# sensorTest.net
KiCad netlist of a schematic drawn in Altium Designer
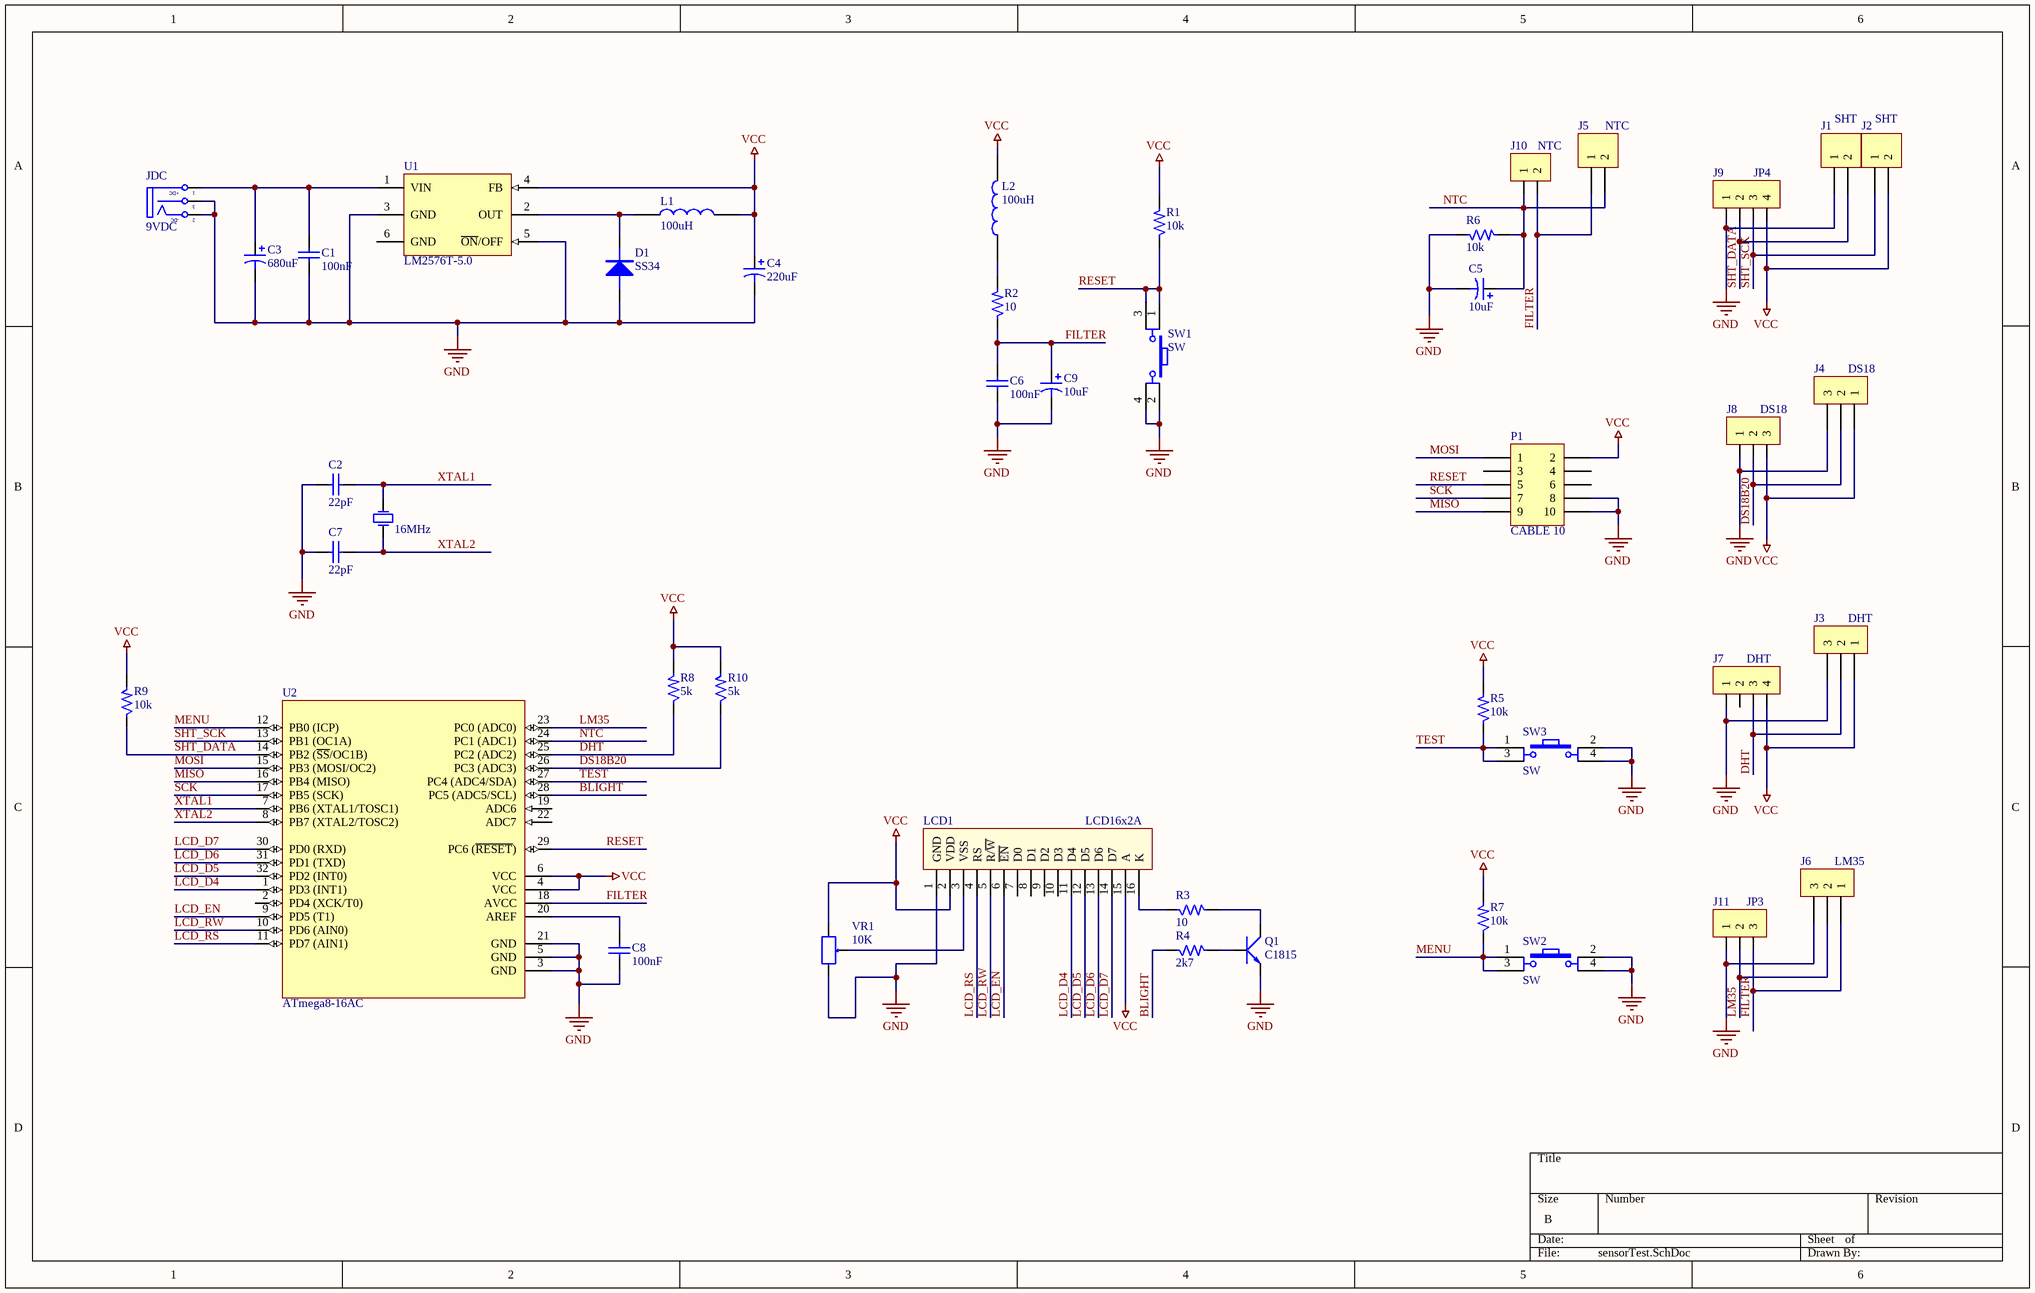
[diagram p0: sensorTest.SchDoc]

(export (version "E")
  (design (tool "Eeschema 10.0.6"))
  (components
    (comp (ref "C1")
      (value "100nF")
      (footprint "Tu 0805")
      (libsource (lib "MH_Thu Vien Du An") (part "CAP 0805"))
    )
    (comp (ref "C2")
      (value "22pF")
      (footprint "Tu 0805")
      (libsource (lib "MH_Thu Vien Du An") (part "Tu 0805"))
    )
    (comp (ref "C3")
      (value "680uF")
      (footprint "C10mm")
      (description "Polarized Capacitor (Axial)")
      (fields (field (name "PUBLISHER") "Altium Limited"))
      (libsource (lib "MH_Thu Vien Du An") (part "Cap Pol 12mm"))
    )
    (comp (ref "C4")
      (value "220uF")
      (footprint "C10mm")
      (description "Polarized Capacitor (Axial)")
      (fields (field (name "PUBLISHER") "Altium Limited"))
      (libsource (lib "MH_Thu Vien Du An") (part "Cap Pol 12mm"))
    )
    (comp (ref "C5")
      (value "10uF")
      (footprint "C5mm")
      (description "Polarized Capacitor (Axial)")
      (fields (field (name "PUBLISHER") "Altium Limited"))
      (libsource (lib "MH_Thu Vien Du An") (part "Cap Pol 5mm"))
    )
    (comp (ref "C6")
      (value "100nF")
      (footprint "Tu 0805")
      (libsource (lib "MH_Thu Vien Du An") (part "CAP 0805"))
    )
    (comp (ref "C7")
      (value "22pF")
      (footprint "Tu 0805")
      (libsource (lib "MH_Thu Vien Du An") (part "CAP 0805"))
    )
    (comp (ref "C8")
      (value "100nF")
      (footprint "Tu 0805")
      (libsource (lib "MH_Thu Vien Du An") (part "CAP 0805"))
    )
    (comp (ref "C9")
      (value "10uF")
      (footprint "C5mm")
      (description "Polarized Capacitor (Axial)")
      (fields (field (name "PUBLISHER") "Altium Limited"))
      (libsource (lib "MH_Thu Vien Du An") (part "Cap Pol 5mm"))
    )
    (comp (ref "D1")
      (value "SS34")
      (footprint "SMB")
      (description "Diode SS34 3A 40V SMA ( 1N5822 SS34A)")
      (libsource (lib "NamTEch_Lib") (part "Diode SS34 3A 40V SMA ( 1N5822 SS34A)_MH"))
    )
    (comp (ref "J1")
      (value "SHT")
      (footprint "KF2-5.08")
      (fields
        (field (name "MANUFACTURER") "Würth Elektronik eiSos GmbH")
        (field (name "PARTNO") "691103110002")
        (field (name "CREATED BY") "Karrer Zheng")
      )
      (libsource (lib "LIBRARY") (part "KF2"))
    )
    (comp (ref "J2")
      (value "SHT")
      (footprint "KF2-5.08")
      (fields
        (field (name "MANUFACTURER") "Würth Elektronik eiSos GmbH")
        (field (name "PARTNO") "691103110002")
        (field (name "CREATED BY") "Karrer Zheng")
      )
      (libsource (lib "LIBRARY") (part "KF2"))
    )
    (comp (ref "J3")
      (value "DHT")
      (footprint "KF3-5.08")
      (fields
        (field (name "MANUFACTURER") "Würth Elektronik eiSos GmbH")
        (field (name "PARTNO") "691103110003")
        (field (name "CREATED BY") "Karrer Zheng")
      )
      (libsource (lib "LIBRARY") (part "KF3"))
    )
    (comp (ref "J4")
      (value "DS18")
      (footprint "KF3-5.08")
      (fields
        (field (name "MANUFACTURER") "Würth Elektronik eiSos GmbH")
        (field (name "PARTNO") "691103110003")
        (field (name "CREATED BY") "Karrer Zheng")
      )
      (libsource (lib "LIBRARY") (part "KF3"))
    )
    (comp (ref "J5")
      (value "NTC")
      (footprint "KF2-5.08")
      (fields
        (field (name "MANUFACTURER") "Würth Elektronik eiSos GmbH")
        (field (name "PARTNO") "691103110002")
        (field (name "CREATED BY") "Karrer Zheng")
      )
      (libsource (lib "LIBRARY") (part "KF2"))
    )
    (comp (ref "J6")
      (value "LM35")
      (footprint "KF3-5.08")
      (fields
        (field (name "MANUFACTURER") "Würth Elektronik eiSos GmbH")
        (field (name "PARTNO") "691103110003")
        (field (name "CREATED BY") "Karrer Zheng")
      )
      (libsource (lib "LIBRARY") (part "KF3"))
    )
    (comp (ref "J7")
      (value "DHT")
      (footprint "JP4-C1T")
      (description "WR-PHD 2.54 mm Angled Socket Header")
      (fields
        (field (name "MANUFACTURER") "Würth Elektronik eiSos GmbH")
        (field (name "PARTNO") "613004143121")
        (field (name "CREATED BY") "Karrer Zheng")
      )
      (libsource (lib "LIBRARY") (part "JP4"))
    )
    (comp (ref "J8")
      (value "DS18")
      (footprint "JP3-C1T")
      (description "WR-PHD 2.54 mm Angled Socket Header")
      (fields
        (field (name "MANUFACTURER") "Würth Elektronik eiSos GmbH")
        (field (name "PARTNO") "613003143121")
        (field (name "CREATED BY") "Karrer Zheng")
      )
      (libsource (lib "LIBRARY") (part "JP3"))
    )
    (comp (ref "J9")
      (value "JP4")
      (footprint "JP4-C1T")
      (description "WR-PHD 2.54 mm Angled Socket Header")
      (fields
        (field (name "MANUFACTURER") "Würth Elektronik eiSos GmbH")
        (field (name "PARTNO") "613004143121")
        (field (name "CREATED BY") "Karrer Zheng")
      )
      (libsource (lib "LIBRARY") (part "JP4"))
    )
    (comp (ref "J10")
      (value "NTC")
      (footprint "JP2-C1T")
      (description "WR-PHD 2.54 mm Angled Socket Header")
      (fields
        (field (name "MANUFACTURER") "Würth Elektronik eiSos GmbH")
        (field (name "PARTNO") "613002143121")
        (field (name "CREATED BY") "Karrer Zheng")
      )
      (libsource (lib "LIBRARY") (part "JP2"))
    )
    (comp (ref "J11")
      (value "JP3")
      (footprint "JP3-C1T")
      (description "WR-PHD 2.54 mm Angled Socket Header")
      (fields
        (field (name "MANUFACTURER") "Würth Elektronik eiSos GmbH")
        (field (name "PARTNO") "613003143121")
        (field (name "CREATED BY") "Karrer Zheng")
      )
      (libsource (lib "LIBRARY") (part "JP3"))
    )
    (comp (ref "JDC")
      (value "9VDC")
      (footprint "DC-IN")
      (description "Jac DC input")
      (libsource (lib "NamTEch_Lib") (part "DCIN"))
    )
    (comp (ref "L1")
      (value "100uH")
      (footprint "Cuon Cam 7.5x7x5")
      (description "Dán")
      (libsource (lib "THU VIEN SCH_04042017_1") (part "CUON CAM 100uH_SMD"))
    )
    (comp (ref "L2")
      (value "100uH")
      (footprint "Cuon Cam 7.5x7x5")
      (description "Dán")
      (libsource (lib "") (part "CUON CAM 100uH_SMD_1"))
    )
    (comp (ref "LCD1")
      (value "LCD16x2A")
      (footprint "LCD16X2")
      (description "LCD dipslay 16 char, 2 line")
      (libsource (lib "MH_Thu Vien Du An") (part "LCD16x2"))
    )
    (comp (ref "P1")
      (value "CABLE 10")
      (footprint "CABLE 10")
      (description "Header, 5-Pin, Dual row")
      (fields (field (name "PUBLISHER") "Altium Limited"))
      (libsource (lib "MH_Thu Vien Du An") (part "CABLE 10"))
    )
    (comp (ref "Q1")
      (value "C1815")
      (footprint "SOT23B")
      (description "NPN 600mW, ECB")
      (libsource (lib "syhaunguyen") (part "C1815"))
    )
    (comp (ref "R1")
      (value "10k")
      (footprint "Tro SMD 0805")
      (description "Resistor 1/4W")
      (libsource (lib "MH_Thu Vien Du An") (part "Res"))
    )
    (comp (ref "R2")
      (value "10")
      (footprint "Tro SMD 0805")
      (description "Resistor 1/4W")
      (libsource (lib "MH_Thu Vien Du An") (part "Res"))
    )
    (comp (ref "R3")
      (value "10")
      (footprint "Tro SMD 0805")
      (description "Resistor 1/4W")
      (libsource (lib "MH_Thu Vien Du An") (part "Res"))
    )
    (comp (ref "R4")
      (value "2k7")
      (footprint "Tro SMD 0805")
      (description "Resistor 1/4W")
      (libsource (lib "MH_Thu Vien Du An") (part "Res"))
    )
    (comp (ref "R5")
      (value "10k")
      (footprint "Tro SMD 0805")
      (description "Resistor 1/4W")
      (libsource (lib "MH_Thu Vien Du An") (part "Res"))
    )
    (comp (ref "R6")
      (value "10k")
      (footprint "Tro SMD 0805")
      (description "Resistor 1/4W")
      (libsource (lib "MH_Thu Vien Du An") (part "Res"))
    )
    (comp (ref "R7")
      (value "10k")
      (footprint "Tro SMD 0805")
      (description "Resistor 1/4W")
      (libsource (lib "MH_Thu Vien Du An") (part "Res"))
    )
    (comp (ref "R8")
      (value "5k")
      (footprint "Tro SMD 0805")
      (description "Resistor 1/4W")
      (libsource (lib "MH_Thu Vien Du An") (part "Res"))
    )
    (comp (ref "R9")
      (value "10k")
      (footprint "Tro SMD 0805")
      (description "Resistor 1/4W")
      (libsource (lib "MH_Thu Vien Du An") (part "Res"))
    )
    (comp (ref "R10")
      (value "5k")
      (footprint "Tro SMD 0805")
      (description "Resistor 1/4W")
      (libsource (lib "MH_Thu Vien Du An") (part "Res"))
    )
    (comp (ref "SW1")
      (value "SW")
      (footprint "SW4")
      (description "Switch button 4 pin")
      (libsource (lib "") (part "SW4_1"))
    )
    (comp (ref "SW2")
      (value "SW")
      (footprint "SW4")
      (description "Switch button 4 pin")
      (libsource (lib "MH_Thu Vien Du An") (part "SW4"))
    )
    (comp (ref "SW3")
      (value "SW")
      (footprint "SW4")
      (description "Switch button 4 pin")
      (libsource (lib "MH_Thu Vien Du An") (part "SW4"))
    )
    (comp (ref "U1")
      (value "LM2576T-5.0")
      (footprint "LM2576SSMD")
      (description "SIMPLE SWITCHER; 3A Step-Down Voltage Regulator")
      (fields
        (field (name "MANUFACTURER") "National Semiconductor")
        (field (name "DIGIKEYPARTNUMBER") "LM2576T-5.0-ND")
        (field (name "PUBLISHER") "Altium Limited")
      )
      (libsource (lib "MH_Thu Vien Du An") (part "LM2576T-5.0"))
    )
    (comp (ref "U2")
      (value "ATmega8-16AC")
      (footprint "32A_L")
      (description "8-Bit AVR Microcontroller with 8K Bytes of In-System Programmable Flash Memory")
      (fields (field (name "PUBLISHER") "Altium Limited"))
      (libsource (lib "MH_Thu Vien Du An") (part "ATmega8-16AC"))
    )
    (comp (ref "VR1")
      (value "10K")
      (footprint "VR")
      (description "Var Resistor")
      (libsource (lib "syhaunguyen") (part "VR"))
    )
    (comp (ref "Y1")
      (value "16MHz")
      (footprint "XT2")
      (description "Crystal Oscillator")
      (fields (field (name "PUBLISHER") "Altium Limited"))
      (libsource (lib "MH_Thu Vien Du An") (part "Crystal"))
    )
  )
  (nets
    (net (code "1") (name "/BLIGHT") (class "Default")
      (node (ref "R4") (pin "1") (pinfunction "1_1") (pintype "passive"))
      (node (ref "U2") (pin "28") (pinfunction "PC5_(ADC5/SCL)_28") (pintype "bidirectional"))
    )
    (net (code "2") (name "/DHT") (class "Default")
      (node (ref "J3") (pin "2") (pinfunction "2_2") (pintype "passive"))
      (node (ref "J7") (pin "3") (pinfunction "3_3") (pintype "passive"))
      (node (ref "R8") (pin "1") (pinfunction "1_1") (pintype "passive"))
      (node (ref "U2") (pin "25") (pinfunction "PC2_(ADC2)_25") (pintype "bidirectional"))
    )
    (net (code "3") (name "/DS18B20") (class "Default")
      (node (ref "J4") (pin "2") (pinfunction "2_2") (pintype "passive"))
      (node (ref "J8") (pin "2") (pinfunction "2_2") (pintype "passive"))
      (node (ref "R10") (pin "1") (pinfunction "1_1") (pintype "passive"))
      (node (ref "U2") (pin "26") (pinfunction "PC3_(ADC3)_26") (pintype "bidirectional"))
    )
    (net (code "4") (name "/FILTER") (class "Default")
      (node (ref "C6") (pin "2") (pinfunction "2_2") (pintype "passive"))
      (node (ref "C9") (pin "1") (pinfunction "1_1") (pintype "passive"))
      (node (ref "J10") (pin "2") (pinfunction "2_2") (pintype "passive"))
      (node (ref "J11") (pin "3") (pinfunction "3_3") (pintype "passive"))
      (node (ref "J5") (pin "1") (pinfunction "1_1") (pintype "passive"))
      (node (ref "J6") (pin "1") (pinfunction "1_1") (pintype "passive"))
      (node (ref "R2") (pin "1") (pinfunction "1_1") (pintype "passive"))
      (node (ref "U2") (pin "18") (pinfunction "AVCC_18") (pintype "power_in"))
    )
    (net (code "5") (name "/LCD_D4") (class "Default")
      (node (ref "LCD1") (pin "11") (pinfunction "D4_11") (pintype "passive"))
      (node (ref "U2") (pin "1") (pinfunction "PD3_(INT1)_1") (pintype "bidirectional"))
    )
    (net (code "6") (name "/LCD_D5") (class "Default")
      (node (ref "LCD1") (pin "12") (pinfunction "D5_12") (pintype "passive"))
      (node (ref "U2") (pin "32") (pinfunction "PD2_(INT0)_32") (pintype "bidirectional"))
    )
    (net (code "7") (name "/LCD_D6") (class "Default")
      (node (ref "LCD1") (pin "13") (pinfunction "D6_13") (pintype "passive"))
      (node (ref "U2") (pin "31") (pinfunction "PD1_(TXD)_31") (pintype "bidirectional"))
    )
    (net (code "8") (name "/LCD_D7") (class "Default")
      (node (ref "LCD1") (pin "14") (pinfunction "D7_14") (pintype "passive"))
      (node (ref "U2") (pin "30") (pinfunction "PD0_(RXD)_30") (pintype "bidirectional"))
    )
    (net (code "9") (name "/LCD_EN") (class "Default")
      (node (ref "LCD1") (pin "6") (pinfunction "~{EN}_6") (pintype "passive"))
      (node (ref "U2") (pin "9") (pinfunction "PD5_(T1)_9") (pintype "bidirectional"))
    )
    (net (code "10") (name "/LCD_RS") (class "Default")
      (node (ref "LCD1") (pin "4") (pinfunction "RS_4") (pintype "passive"))
      (node (ref "U2") (pin "11") (pinfunction "PD7_(AIN1)_11") (pintype "bidirectional"))
    )
    (net (code "11") (name "/LCD_RW") (class "Default")
      (node (ref "LCD1") (pin "5") (pinfunction "R/~{W}_5") (pintype "passive"))
      (node (ref "U2") (pin "10") (pinfunction "PD6_(AIN0)_10") (pintype "bidirectional"))
    )
    (net (code "12") (name "/LM35") (class "Default")
      (node (ref "J11") (pin "2") (pinfunction "2_2") (pintype "passive"))
      (node (ref "J6") (pin "2") (pinfunction "2_2") (pintype "passive"))
      (node (ref "U2") (pin "23") (pinfunction "PC0_(ADC0)_23") (pintype "bidirectional"))
    )
    (net (code "13") (name "/MENU") (class "Default")
      (node (ref "R7") (pin "1") (pinfunction "1_1") (pintype "passive"))
      (node (ref "SW2") (pin "1") (pintype "passive"))
      (node (ref "SW2") (pin "3") (pintype "passive"))
      (node (ref "U2") (pin "12") (pinfunction "PB0_(ICP)_12") (pintype "bidirectional"))
    )
    (net (code "14") (name "/MISO") (class "Default")
      (node (ref "P1") (pin "9") (pinfunction "9_9") (pintype "passive"))
      (node (ref "U2") (pin "16") (pinfunction "PB4_(MISO)_16") (pintype "bidirectional"))
    )
    (net (code "15") (name "/MOSI") (class "Default")
      (node (ref "P1") (pin "1") (pinfunction "1_1") (pintype "passive"))
      (node (ref "U2") (pin "15") (pinfunction "PB3_(MOSI/OC2)_15") (pintype "bidirectional"))
    )
    (net (code "16") (name "/NTC") (class "Default")
      (node (ref "C5") (pin "1") (pinfunction "1_1") (pintype "passive"))
      (node (ref "J10") (pin "1") (pinfunction "1_1") (pintype "passive"))
      (node (ref "J5") (pin "2") (pinfunction "2_2") (pintype "passive"))
      (node (ref "R6") (pin "2") (pinfunction "2_2") (pintype "passive"))
      (node (ref "U2") (pin "24") (pinfunction "PC1_(ADC1)_24") (pintype "bidirectional"))
    )
    (net (code "17") (name "/RESET") (class "Default")
      (node (ref "P1") (pin "5") (pinfunction "5_5") (pintype "passive"))
      (node (ref "R1") (pin "1") (pinfunction "1_1") (pintype "passive"))
      (node (ref "SW1") (pin "1") (pintype "passive"))
      (node (ref "SW1") (pin "3") (pintype "passive"))
      (node (ref "U2") (pin "29") (pinfunction "PC6_(~{RESET})_29") (pintype "bidirectional"))
    )
    (net (code "18") (name "/SCK") (class "Default")
      (node (ref "P1") (pin "7") (pinfunction "7_7") (pintype "passive"))
      (node (ref "U2") (pin "17") (pinfunction "PB5_(SCK)_17") (pintype "bidirectional"))
    )
    (net (code "19") (name "/SHT_DATA") (class "Default")
      (node (ref "J1") (pin "2") (pinfunction "2_2") (pintype "passive"))
      (node (ref "J9") (pin "2") (pinfunction "2_2") (pintype "passive"))
      (node (ref "R9") (pin "1") (pinfunction "1_1") (pintype "passive"))
      (node (ref "U2") (pin "14") (pinfunction "PB2_(~{SS}/OC1B)_14") (pintype "bidirectional"))
    )
    (net (code "20") (name "/SHT_SCK") (class "Default")
      (node (ref "J2") (pin "1") (pinfunction "1_1") (pintype "passive"))
      (node (ref "J9") (pin "3") (pinfunction "3_3") (pintype "passive"))
      (node (ref "U2") (pin "13") (pinfunction "PB1_(OC1A)_13") (pintype "bidirectional"))
    )
    (net (code "21") (name "/TEST") (class "Default")
      (node (ref "R5") (pin "1") (pinfunction "1_1") (pintype "passive"))
      (node (ref "SW3") (pin "1") (pintype "passive"))
      (node (ref "SW3") (pin "3") (pintype "passive"))
      (node (ref "U2") (pin "27") (pinfunction "PC4_(ADC4/SDA)_27") (pintype "bidirectional"))
    )
    (net (code "22") (name "/XTAL1") (class "Default")
      (node (ref "C2") (pin "2") (pinfunction "2_2") (pintype "passive"))
      (node (ref "U2") (pin "7") (pinfunction "PB6_(XTAL1/TOSC1)_7") (pintype "bidirectional"))
      (node (ref "Y1") (pin "2") (pinfunction "OSC2_2") (pintype "passive"))
    )
    (net (code "23") (name "/XTAL2") (class "Default")
      (node (ref "C7") (pin "2") (pinfunction "2_2") (pintype "passive"))
      (node (ref "U2") (pin "8") (pinfunction "PB7_(XTAL2/TOSC2)_8") (pintype "bidirectional"))
      (node (ref "Y1") (pin "1") (pinfunction "OSC1_1") (pintype "passive"))
    )
    (net (code "24") (name "GND") (class "Default")
      (node (ref "C1") (pin "1") (pinfunction "1_1") (pintype "passive"))
      (node (ref "C2") (pin "1") (pinfunction "1_1") (pintype "passive"))
      (node (ref "C3") (pin "2") (pinfunction "2_2") (pintype "passive"))
      (node (ref "C4") (pin "2") (pinfunction "2_2") (pintype "passive"))
      (node (ref "C5") (pin "2") (pinfunction "2_2") (pintype "passive"))
      (node (ref "C6") (pin "1") (pinfunction "1_1") (pintype "passive"))
      (node (ref "C7") (pin "1") (pinfunction "1_1") (pintype "passive"))
      (node (ref "C8") (pin "1") (pinfunction "1_1") (pintype "passive"))
      (node (ref "C9") (pin "2") (pinfunction "2_2") (pintype "passive"))
      (node (ref "D1") (pin "1") (pinfunction "1_1") (pintype "passive"))
      (node (ref "J1") (pin "1") (pinfunction "1_1") (pintype "passive"))
      (node (ref "J11") (pin "1") (pinfunction "1_1") (pintype "passive"))
      (node (ref "J3") (pin "3") (pinfunction "3_3") (pintype "passive"))
      (node (ref "J4") (pin "3") (pinfunction "3_3") (pintype "passive"))
      (node (ref "J6") (pin "3") (pinfunction "3_3") (pintype "passive"))
      (node (ref "J7") (pin "1") (pinfunction "1_1") (pintype "passive"))
      (node (ref "J8") (pin "1") (pinfunction "1_1") (pintype "passive"))
      (node (ref "J9") (pin "1") (pinfunction "1_1") (pintype "passive"))
      (node (ref "JDC") (pin "2") (pinfunction "TN_2") (pintype "passive"))
      (node (ref "JDC") (pin "3") (pinfunction "S_3") (pintype "power_in"))
      (node (ref "LCD1") (pin "1") (pinfunction "GND_1") (pintype "passive"))
      (node (ref "P1") (pin "10") (pinfunction "10_10") (pintype "passive"))
      (node (ref "P1") (pin "8") (pinfunction "8_8") (pintype "passive"))
      (node (ref "Q1") (pin "1") (pinfunction "E_1") (pintype "passive"))
      (node (ref "R6") (pin "1") (pinfunction "1_1") (pintype "passive"))
      (node (ref "SW1") (pin "2") (pintype "passive"))
      (node (ref "SW1") (pin "4") (pintype "passive"))
      (node (ref "SW2") (pin "2") (pintype "passive"))
      (node (ref "SW2") (pin "4") (pintype "passive"))
      (node (ref "SW3") (pin "2") (pintype "passive"))
      (node (ref "SW3") (pin "4") (pintype "passive"))
      (node (ref "U1") (pin "3") (pinfunction "GND_3") (pintype "power_in"))
      (node (ref "U1") (pin "5") (pinfunction "~{ON}/OFF_5") (pintype "input"))
      (node (ref "U2") (pin "21") (pinfunction "GND_21") (pintype "power_in"))
      (node (ref "U2") (pin "3") (pinfunction "GND_3") (pintype "power_in"))
      (node (ref "U2") (pin "5") (pinfunction "GND_5") (pintype "power_in"))
      (node (ref "VR1") (pin "3") (pinfunction "3_3") (pintype "passive"))
    )
    (net (code "25") (name "Net-(JDC-T)") (class "Default")
      (node (ref "C1") (pin "2") (pinfunction "2_2") (pintype "passive"))
      (node (ref "C3") (pin "1") (pinfunction "1_1") (pintype "passive"))
      (node (ref "JDC") (pin "1") (pinfunction "T_1") (pintype "passive"))
      (node (ref "U1") (pin "1") (pinfunction "VIN_1") (pintype "power_in"))
    )
    (net (code "26") (name "Net-(L2-Pad1)") (class "Default")
      (node (ref "L2") (pin "1") (pinfunction "1_1") (pintype "passive"))
      (node (ref "R2") (pin "2") (pinfunction "2_2") (pintype "passive"))
    )
    (net (code "27") (name "Net-(LCD1-K)") (class "Default")
      (node (ref "LCD1") (pin "16") (pinfunction "K_16") (pintype "passive"))
      (node (ref "R3") (pin "1") (pinfunction "1_1") (pintype "passive"))
    )
    (net (code "28") (name "Net-(LCD1-VSS)") (class "Default")
      (node (ref "LCD1") (pin "3") (pinfunction "VSS_3") (pintype "passive"))
      (node (ref "VR1") (pin "2") (pinfunction "2_2") (pintype "passive"))
    )
    (net (code "29") (name "Net-(Q1-B)") (class "Default")
      (node (ref "Q1") (pin "3") (pinfunction "B_3") (pintype "passive"))
      (node (ref "R4") (pin "2") (pinfunction "2_2") (pintype "passive"))
    )
    (net (code "30") (name "Net-(Q1-C)") (class "Default")
      (node (ref "Q1") (pin "2") (pinfunction "C_2") (pintype "passive"))
      (node (ref "R3") (pin "2") (pinfunction "2_2") (pintype "passive"))
    )
    (net (code "31") (name "Net-(U1-OUT)") (class "Default")
      (node (ref "D1") (pin "2") (pinfunction "2_2") (pintype "passive"))
      (node (ref "L1") (pin "1") (pinfunction "1_1") (pintype "passive"))
      (node (ref "U1") (pin "2") (pinfunction "OUT_2") (pintype "power_in"))
    )
    (net (code "32") (name "Net-(U2-AREF)") (class "Default")
      (node (ref "C8") (pin "2") (pinfunction "2_2") (pintype "passive"))
      (node (ref "U2") (pin "20") (pinfunction "AREF_20") (pintype "passive"))
    )
    (net (code "33") (name "VCC") (class "Default")
      (node (ref "C4") (pin "1") (pinfunction "1_1") (pintype "passive"))
      (node (ref "J2") (pin "2") (pinfunction "2_2") (pintype "passive"))
      (node (ref "J3") (pin "1") (pinfunction "1_1") (pintype "passive"))
      (node (ref "J4") (pin "1") (pinfunction "1_1") (pintype "passive"))
      (node (ref "J7") (pin "4") (pinfunction "4_4") (pintype "passive"))
      (node (ref "J8") (pin "3") (pinfunction "3_3") (pintype "passive"))
      (node (ref "J9") (pin "4") (pinfunction "4_4") (pintype "passive"))
      (node (ref "L1") (pin "2") (pinfunction "2_2") (pintype "passive"))
      (node (ref "L2") (pin "2") (pinfunction "2_2") (pintype "passive"))
      (node (ref "LCD1") (pin "15") (pinfunction "A_15") (pintype "passive"))
      (node (ref "LCD1") (pin "2") (pinfunction "VDD_2") (pintype "passive"))
      (node (ref "P1") (pin "2") (pinfunction "2_2") (pintype "passive"))
      (node (ref "R1") (pin "2") (pinfunction "2_2") (pintype "passive"))
      (node (ref "R10") (pin "2") (pinfunction "2_2") (pintype "passive"))
      (node (ref "R5") (pin "2") (pinfunction "2_2") (pintype "passive"))
      (node (ref "R7") (pin "2") (pinfunction "2_2") (pintype "passive"))
      (node (ref "R8") (pin "2") (pinfunction "2_2") (pintype "passive"))
      (node (ref "R9") (pin "2") (pinfunction "2_2") (pintype "passive"))
      (node (ref "U1") (pin "4") (pinfunction "FB_4") (pintype "input"))
      (node (ref "U2") (pin "4") (pinfunction "VCC_4") (pintype "power_in"))
      (node (ref "U2") (pin "6") (pinfunction "VCC_6") (pintype "power_in"))
      (node (ref "VR1") (pin "1") (pinfunction "1_1") (pintype "passive"))
    )
    (net (code "34") (name "unconnected-(J7-Pad2)") (class "Default")
      (node (ref "J7") (pin "2") (pinfunction "2_2") (pintype "passive"))
    )
    (net (code "35") (name "unconnected-(LCD1-D0-Pad7)") (class "Default")
      (node (ref "LCD1") (pin "7") (pinfunction "D0_7") (pintype "passive"))
    )
    (net (code "36") (name "unconnected-(LCD1-D1-Pad8)") (class "Default")
      (node (ref "LCD1") (pin "8") (pinfunction "D1_8") (pintype "passive"))
    )
    (net (code "37") (name "unconnected-(LCD1-D2-Pad9)") (class "Default")
      (node (ref "LCD1") (pin "9") (pinfunction "D2_9") (pintype "passive"))
    )
    (net (code "38") (name "unconnected-(LCD1-D3-Pad10)") (class "Default")
      (node (ref "LCD1") (pin "10") (pinfunction "D3_10") (pintype "passive"))
    )
    (net (code "39") (name "unconnected-(P1-Pad3)") (class "Default")
      (node (ref "P1") (pin "3") (pinfunction "3_3") (pintype "passive"))
    )
    (net (code "40") (name "unconnected-(P1-Pad4)") (class "Default")
      (node (ref "P1") (pin "4") (pinfunction "4_4") (pintype "passive"))
    )
    (net (code "41") (name "unconnected-(P1-Pad6)") (class "Default")
      (node (ref "P1") (pin "6") (pinfunction "6_6") (pintype "passive"))
    )
    (net (code "42") (name "unconnected-(U1-GND-Pad6)") (class "Default")
      (node (ref "U1") (pin "6") (pinfunction "GND_6") (pintype "passive"))
    )
    (net (code "43") (name "unconnected-(U2-ADC6-Pad19)") (class "Default")
      (node (ref "U2") (pin "19") (pinfunction "ADC6_19") (pintype "input"))
    )
    (net (code "44") (name "unconnected-(U2-ADC7-Pad22)") (class "Default")
      (node (ref "U2") (pin "22") (pinfunction "ADC7_22") (pintype "input"))
    )
    (net (code "45") (name "unconnected-(U2-PD4_(XCK{slash}T0)-Pad2)") (class "Default")
      (node (ref "U2") (pin "2") (pinfunction "PD4_(XCK/T0)_2") (pintype "bidirectional"))
    )
  )
)
